# dbg-ram-4x8K.net
KiCad netlist of a schematic drawn in EAGLE
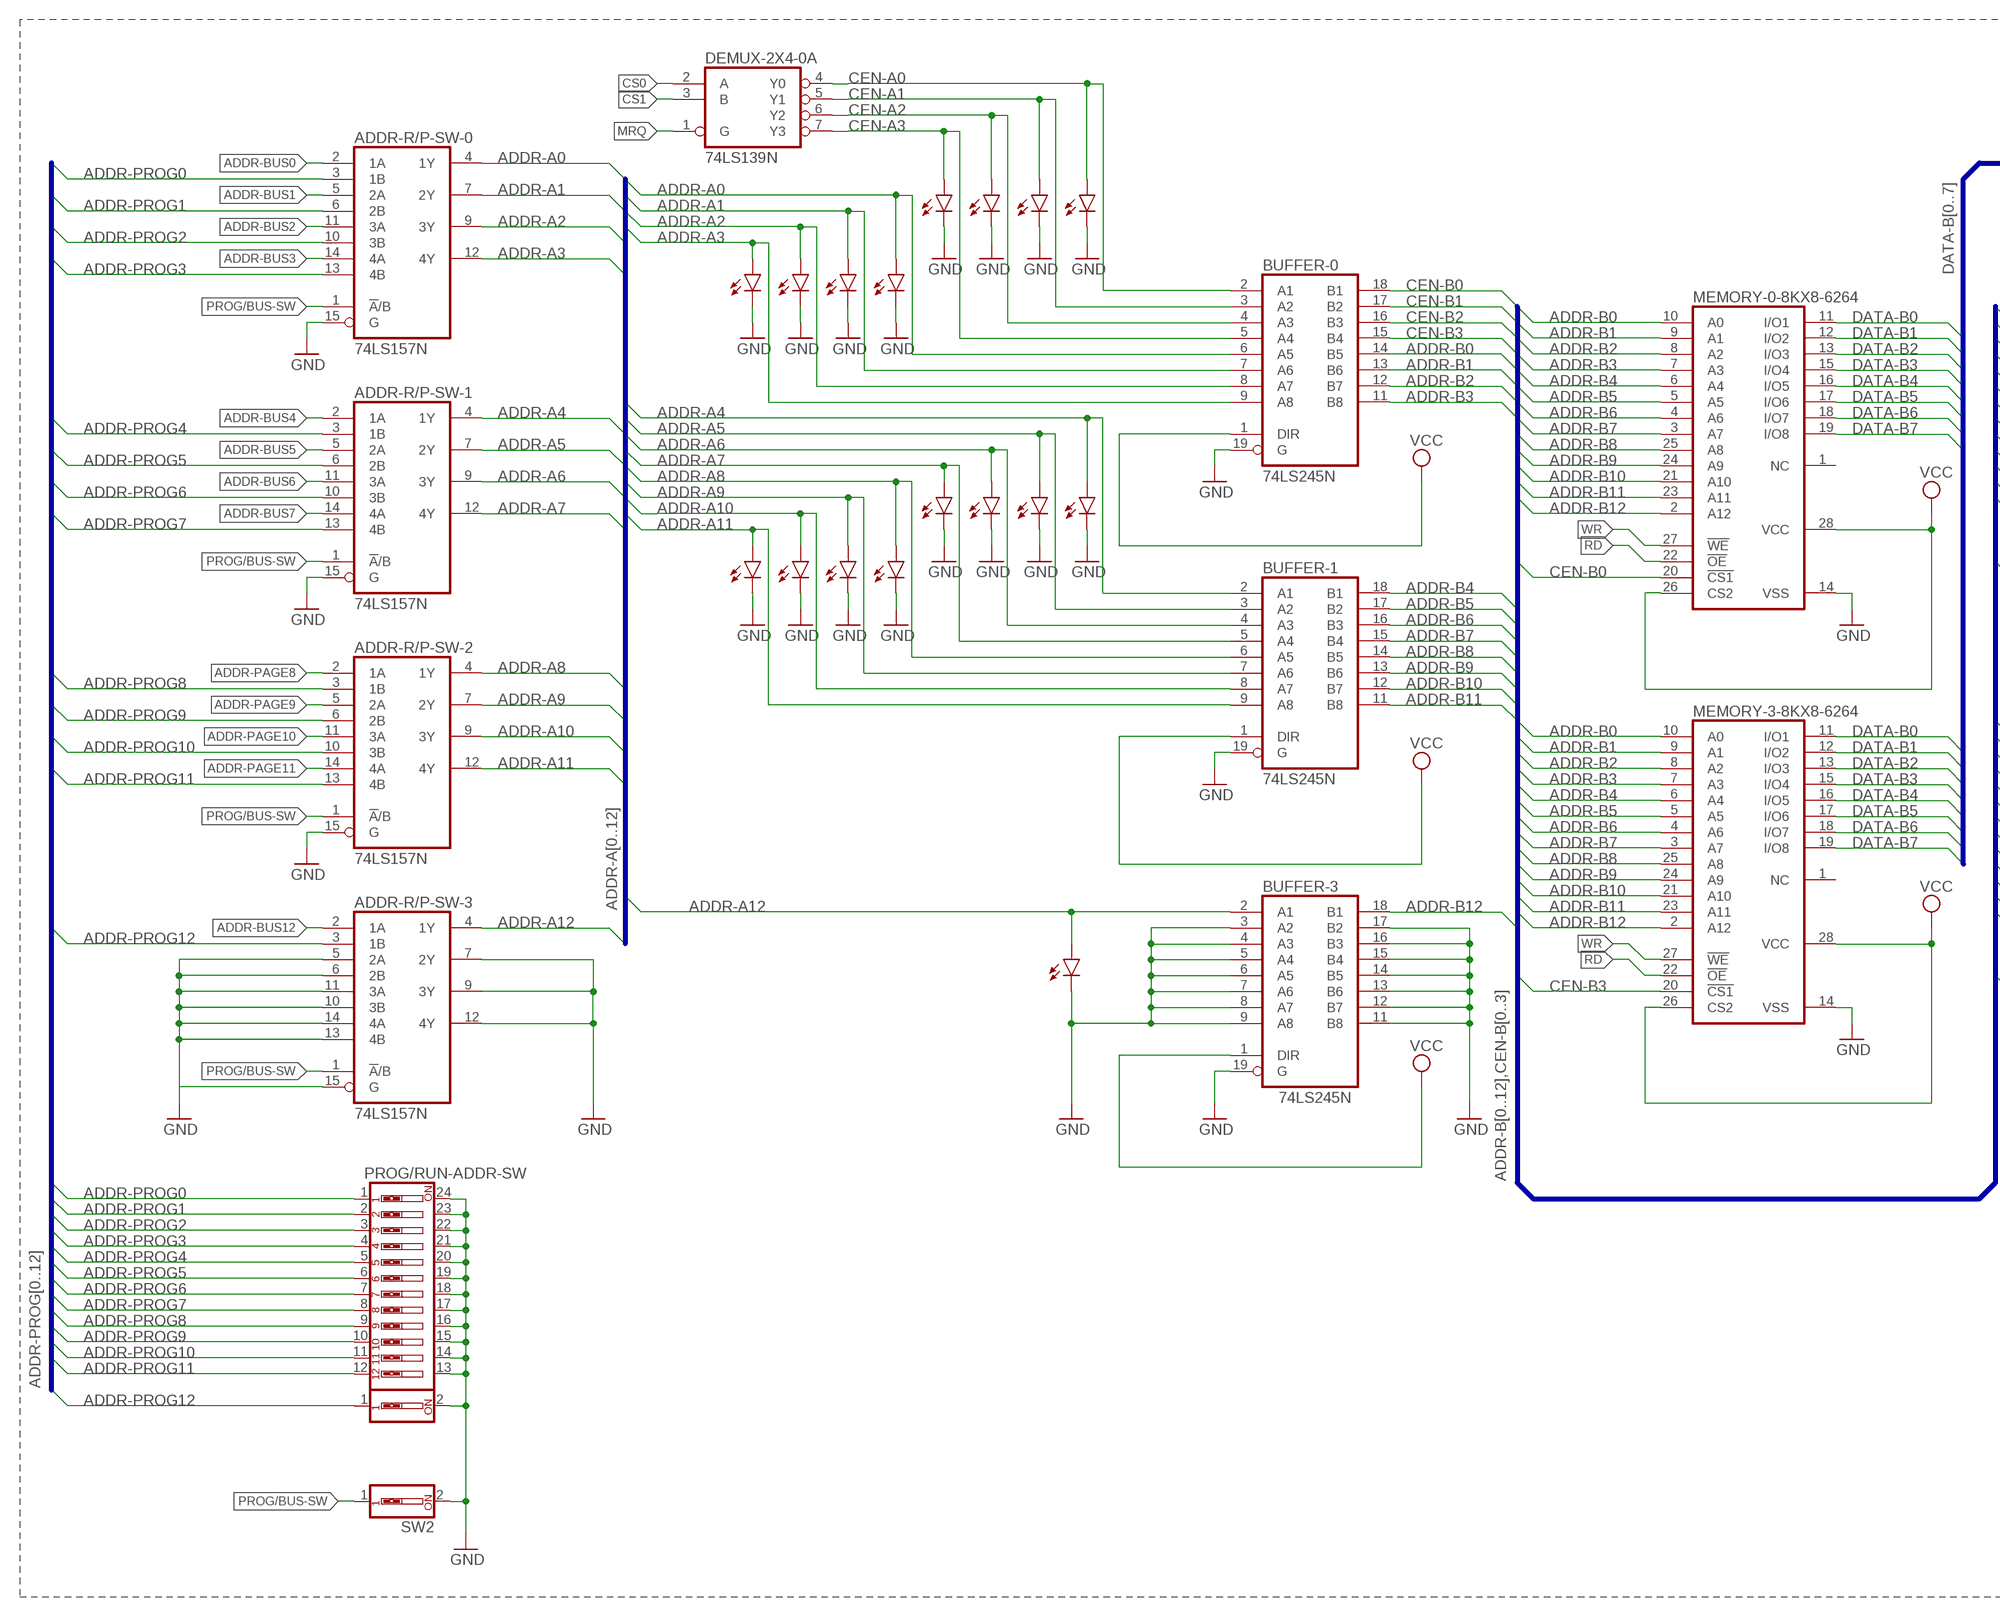
[diagram p0: schematic, sheet 1, part 1 of 2]
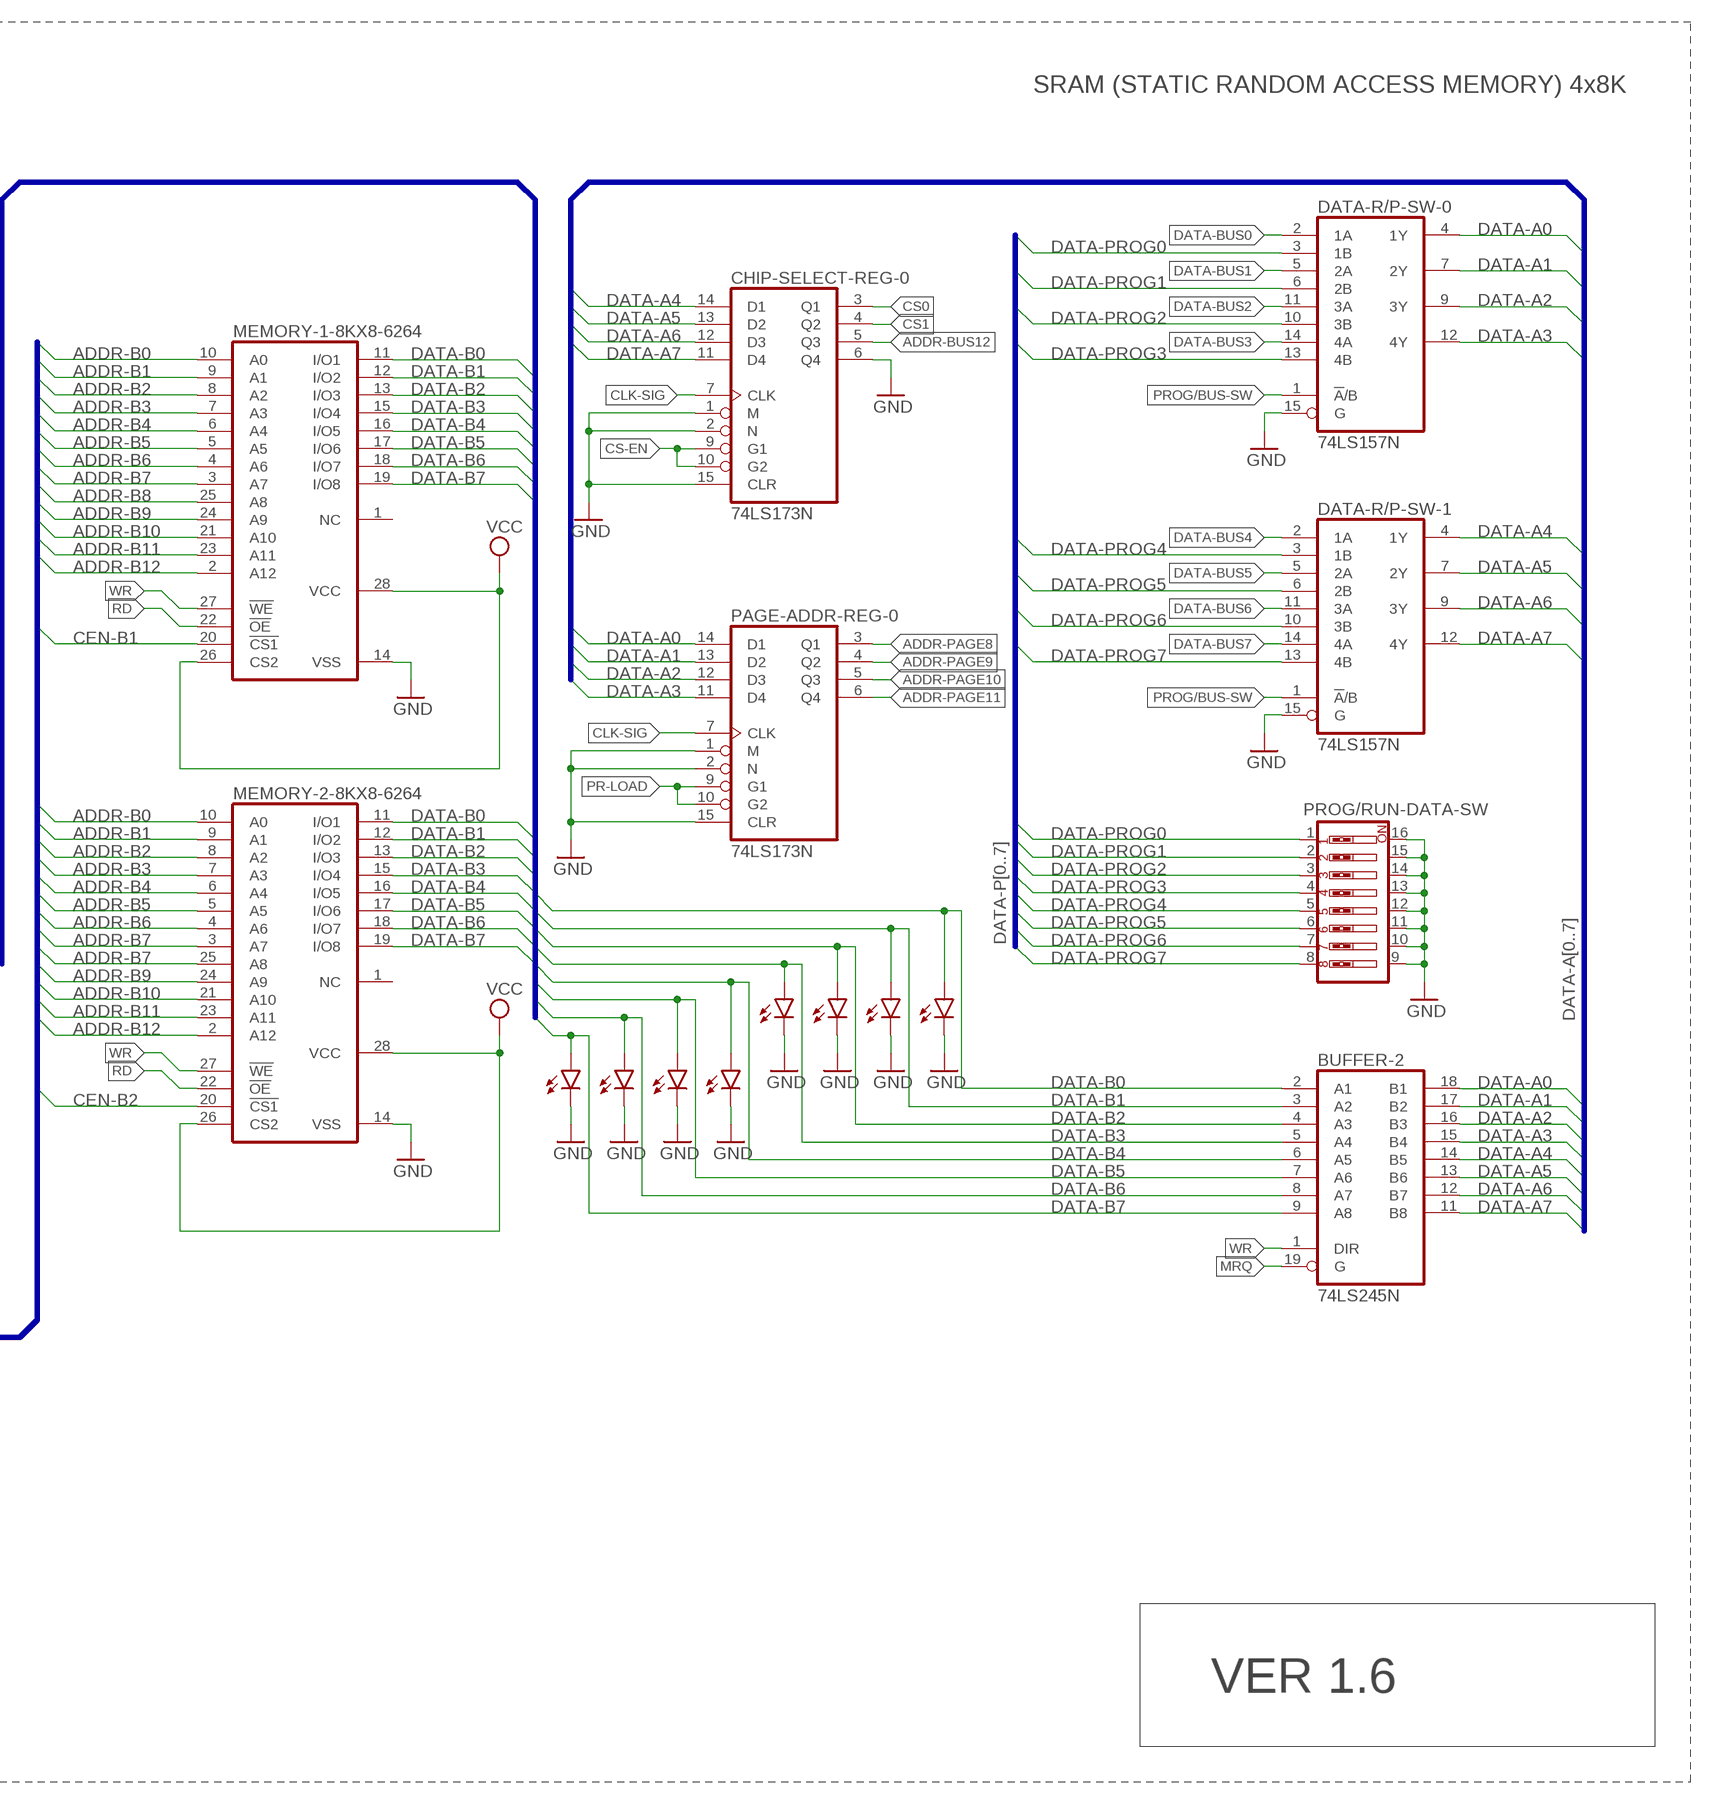
[diagram p1: schematic, sheet 1, part 2 of 2]

(export (version "E")
  (design (tool "Eeschema 10.0.6"))
  (components
    (comp (ref "ADDR-R/P-SW-0")
      (value "74LS157N")
      (footprint "eagle-import:DIL16")
      (libsource (lib "eagle-import") (part "74157NLS"))
    )
    (comp (ref "ADDR-R/P-SW-1")
      (value "74LS157N")
      (footprint "eagle-import:DIL16")
      (libsource (lib "eagle-import") (part "74157NLS"))
    )
    (comp (ref "ADDR-R/P-SW-2")
      (value "74LS157N")
      (footprint "eagle-import:DIL16")
      (libsource (lib "eagle-import") (part "74157NLS"))
    )
    (comp (ref "ADDR-R/P-SW-3")
      (value "74LS157N")
      (footprint "eagle-import:DIL16")
      (libsource (lib "eagle-import") (part "74157NLS"))
    )
    (comp (ref "BUFFER-0")
      (value "74LS245N")
      (footprint "eagle-import:DIL20")
      (libsource (lib "eagle-import") (part "74245NLS"))
    )
    (comp (ref "BUFFER-1")
      (value "74LS245N")
      (footprint "eagle-import:DIL20")
      (libsource (lib "eagle-import") (part "74245NLS"))
    )
    (comp (ref "BUFFER-2")
      (value "74LS245N")
      (footprint "eagle-import:DIL20")
      (libsource (lib "eagle-import") (part "74245NLS"))
    )
    (comp (ref "BUFFER-3")
      (value "74LS245N")
      (footprint "eagle-import:DIL20")
      (libsource (lib "eagle-import") (part "74245NLS"))
    )
    (comp (ref "CHIP-SELECT-REG-0")
      (value "74LS173N")
      (footprint "eagle-import:DIL16")
      (libsource (lib "eagle-import") (part "74173NLS"))
    )
    (comp (ref "DATA-R/P-SW-0")
      (value "74LS157N")
      (footprint "eagle-import:DIL16")
      (libsource (lib "eagle-import") (part "74157NLS"))
    )
    (comp (ref "DATA-R/P-SW-1")
      (value "74LS157N")
      (footprint "eagle-import:DIL16")
      (libsource (lib "eagle-import") (part "74157NLS"))
    )
    (comp (ref "DEMUX-2X4-0")
      (value "74LS139N")
      (footprint "eagle-import:DIL16")
      (libsource (lib "eagle-import") (part "74139NLS"))
    )
    (comp (ref "LED1")
      (value "LED5MM")
      (footprint "eagle-import:LED5MM")
      (libsource (lib "eagle-import") (part "LED5MM"))
    )
    (comp (ref "LED2")
      (value "LED5MM")
      (footprint "eagle-import:LED5MM")
      (libsource (lib "eagle-import") (part "LED5MM"))
    )
    (comp (ref "LED3")
      (value "LED5MM")
      (footprint "eagle-import:LED5MM")
      (libsource (lib "eagle-import") (part "LED5MM"))
    )
    (comp (ref "LED4")
      (value "LED5MM")
      (footprint "eagle-import:LED5MM")
      (libsource (lib "eagle-import") (part "LED5MM"))
    )
    (comp (ref "LED5")
      (value "LED5MM")
      (footprint "eagle-import:LED5MM")
      (libsource (lib "eagle-import") (part "LED5MM"))
    )
    (comp (ref "LED6")
      (value "LED5MM")
      (footprint "eagle-import:LED5MM")
      (libsource (lib "eagle-import") (part "LED5MM"))
    )
    (comp (ref "LED7")
      (value "LED5MM")
      (footprint "eagle-import:LED5MM")
      (libsource (lib "eagle-import") (part "LED5MM"))
    )
    (comp (ref "LED8")
      (value "LED5MM")
      (footprint "eagle-import:LED5MM")
      (libsource (lib "eagle-import") (part "LED5MM"))
    )
    (comp (ref "LED9")
      (value "LED5MM")
      (footprint "eagle-import:LED5MM")
      (libsource (lib "eagle-import") (part "LED5MM"))
    )
    (comp (ref "LED10")
      (value "LED5MM")
      (footprint "eagle-import:LED5MM")
      (libsource (lib "eagle-import") (part "LED5MM"))
    )
    (comp (ref "LED11")
      (value "LED5MM")
      (footprint "eagle-import:LED5MM")
      (libsource (lib "eagle-import") (part "LED5MM"))
    )
    (comp (ref "LED12")
      (value "LED5MM")
      (footprint "eagle-import:LED5MM")
      (libsource (lib "eagle-import") (part "LED5MM"))
    )
    (comp (ref "LED13")
      (value "LED5MM")
      (footprint "eagle-import:LED5MM")
      (libsource (lib "eagle-import") (part "LED5MM"))
    )
    (comp (ref "LED14")
      (value "LED5MM")
      (footprint "eagle-import:LED5MM")
      (libsource (lib "eagle-import") (part "LED5MM"))
    )
    (comp (ref "LED15")
      (value "LED5MM")
      (footprint "eagle-import:LED5MM")
      (libsource (lib "eagle-import") (part "LED5MM"))
    )
    (comp (ref "LED16")
      (value "LED5MM")
      (footprint "eagle-import:LED5MM")
      (libsource (lib "eagle-import") (part "LED5MM"))
    )
    (comp (ref "LED17")
      (value "LED5MM")
      (footprint "eagle-import:LED5MM")
      (libsource (lib "eagle-import") (part "LED5MM"))
    )
    (comp (ref "LED18")
      (value "LED5MM")
      (footprint "eagle-import:LED5MM")
      (libsource (lib "eagle-import") (part "LED5MM"))
    )
    (comp (ref "LED19")
      (value "LED5MM")
      (footprint "eagle-import:LED5MM")
      (libsource (lib "eagle-import") (part "LED5MM"))
    )
    (comp (ref "LED20")
      (value "LED5MM")
      (footprint "eagle-import:LED5MM")
      (libsource (lib "eagle-import") (part "LED5MM"))
    )
    (comp (ref "LED21")
      (value "LED5MM")
      (footprint "eagle-import:LED5MM")
      (libsource (lib "eagle-import") (part "LED5MM"))
    )
    (comp (ref "LED22")
      (value "LED5MM")
      (footprint "eagle-import:LED5MM")
      (libsource (lib "eagle-import") (part "LED5MM"))
    )
    (comp (ref "LED23")
      (value "LED5MM")
      (footprint "eagle-import:LED5MM")
      (libsource (lib "eagle-import") (part "LED5MM"))
    )
    (comp (ref "LED24")
      (value "LED5MM")
      (footprint "eagle-import:LED5MM")
      (libsource (lib "eagle-import") (part "LED5MM"))
    )
    (comp (ref "LED25")
      (value "LED5MM")
      (footprint "eagle-import:LED5MM")
      (libsource (lib "eagle-import") (part "LED5MM"))
    )
    (comp (ref "MEMORY-0-8KX8-6264")
      (value "6264A")
      (footprint "eagle-import:DIL28-6")
      (libsource (lib "eagle-import") (part "6264A"))
    )
    (comp (ref "MEMORY-1-8KX8-6264")
      (value "6264A")
      (footprint "eagle-import:DIL28-6")
      (libsource (lib "eagle-import") (part "6264A"))
    )
    (comp (ref "MEMORY-2-8KX8-6264")
      (value "6264A")
      (footprint "eagle-import:DIL28-6")
      (libsource (lib "eagle-import") (part "6264A"))
    )
    (comp (ref "MEMORY-3-8KX8-6264")
      (value "6264A")
      (footprint "eagle-import:DIL28-6")
      (libsource (lib "eagle-import") (part "6264A"))
    )
    (comp (ref "PAGE-ADDR-REG-0")
      (value "74LS173N")
      (footprint "eagle-import:DIL16")
      (libsource (lib "eagle-import") (part "74173NLS"))
    )
    (comp (ref "PROG/RUN-ADDR-SW")
      (value "SW_DIP-12")
      (footprint "eagle-import:EDG-12")
      (libsource (lib "eagle-import") (part "SW_DIP-12"))
    )
    (comp (ref "PROG/RUN-DATA-SW")
      (value "SW_DIP-8")
      (footprint "eagle-import:EDG-08")
      (libsource (lib "eagle-import") (part "SW_DIP-8"))
    )
    (comp (ref "SW2")
      (value "SW_DIP-1")
      (footprint "eagle-import:EDG-01")
      (libsource (lib "eagle-import") (part "SW_DIP-1"))
    )
    (comp (ref "SW3")
      (value "SW_DIP-1")
      (footprint "eagle-import:EDG-01")
      (libsource (lib "eagle-import") (part "SW_DIP-1"))
    )
  )
  (nets
    (net (code "9") (name "/ADDR-A0") (class "Default")
      (node (ref "ADDR-R/P-SW-0") (pin "4") (pinfunction "1Y_4") (pintype "output"))
      (node (ref "BUFFER-0") (pin "6") (pinfunction "A5_6") (pintype "bidirectional"))
      (node (ref "LED1") (pin "A") (pinfunction "A_A") (pintype "passive"))
    )
    (net (code "10") (name "/ADDR-A1") (class "Default")
      (node (ref "ADDR-R/P-SW-0") (pin "7") (pinfunction "2Y_7") (pintype "output"))
      (node (ref "BUFFER-0") (pin "7") (pinfunction "A6_7") (pintype "bidirectional"))
      (node (ref "LED2") (pin "A") (pinfunction "A_A") (pintype "passive"))
    )
    (net (code "11") (name "/ADDR-A2") (class "Default")
      (node (ref "ADDR-R/P-SW-0") (pin "9") (pinfunction "3Y_9") (pintype "output"))
      (node (ref "BUFFER-0") (pin "8") (pinfunction "A7_8") (pintype "bidirectional"))
      (node (ref "LED3") (pin "A") (pinfunction "A_A") (pintype "passive"))
    )
    (net (code "12") (name "/ADDR-A3") (class "Default")
      (node (ref "ADDR-R/P-SW-0") (pin "12") (pinfunction "4Y_12") (pintype "output"))
      (node (ref "BUFFER-0") (pin "9") (pinfunction "A8_9") (pintype "bidirectional"))
      (node (ref "LED4") (pin "A") (pinfunction "A_A") (pintype "passive"))
    )
    (net (code "13") (name "/ADDR-A4") (class "Default")
      (node (ref "ADDR-R/P-SW-1") (pin "4") (pinfunction "1Y_4") (pintype "output"))
      (node (ref "BUFFER-1") (pin "2") (pinfunction "A1_2") (pintype "bidirectional"))
      (node (ref "LED5") (pin "A") (pinfunction "A_A") (pintype "passive"))
    )
    (net (code "14") (name "/ADDR-A5") (class "Default")
      (node (ref "ADDR-R/P-SW-1") (pin "7") (pinfunction "2Y_7") (pintype "output"))
      (node (ref "BUFFER-1") (pin "3") (pinfunction "A2_3") (pintype "bidirectional"))
      (node (ref "LED6") (pin "A") (pinfunction "A_A") (pintype "passive"))
    )
    (net (code "15") (name "/ADDR-A6") (class "Default")
      (node (ref "ADDR-R/P-SW-1") (pin "9") (pinfunction "3Y_9") (pintype "output"))
      (node (ref "BUFFER-1") (pin "4") (pinfunction "A3_4") (pintype "bidirectional"))
      (node (ref "LED10") (pin "A") (pinfunction "A_A") (pintype "passive"))
    )
    (net (code "16") (name "/ADDR-A7") (class "Default")
      (node (ref "ADDR-R/P-SW-1") (pin "12") (pinfunction "4Y_12") (pintype "output"))
      (node (ref "BUFFER-1") (pin "5") (pinfunction "A4_5") (pintype "bidirectional"))
      (node (ref "LED7") (pin "A") (pinfunction "A_A") (pintype "passive"))
    )
    (net (code "17") (name "/ADDR-A8") (class "Default")
      (node (ref "ADDR-R/P-SW-2") (pin "4") (pinfunction "1Y_4") (pintype "output"))
      (node (ref "BUFFER-1") (pin "6") (pinfunction "A5_6") (pintype "bidirectional"))
      (node (ref "LED8") (pin "A") (pinfunction "A_A") (pintype "passive"))
    )
    (net (code "18") (name "/ADDR-A9") (class "Default")
      (node (ref "ADDR-R/P-SW-2") (pin "7") (pinfunction "2Y_7") (pintype "output"))
      (node (ref "BUFFER-1") (pin "7") (pinfunction "A6_7") (pintype "bidirectional"))
      (node (ref "LED9") (pin "A") (pinfunction "A_A") (pintype "passive"))
    )
    (net (code "19") (name "/ADDR-A10") (class "Default")
      (node (ref "ADDR-R/P-SW-2") (pin "9") (pinfunction "3Y_9") (pintype "output"))
      (node (ref "BUFFER-1") (pin "8") (pinfunction "A7_8") (pintype "bidirectional"))
      (node (ref "LED15") (pin "A") (pinfunction "A_A") (pintype "passive"))
    )
    (net (code "20") (name "/ADDR-A11") (class "Default")
      (node (ref "ADDR-R/P-SW-2") (pin "12") (pinfunction "4Y_12") (pintype "output"))
      (node (ref "BUFFER-1") (pin "9") (pinfunction "A8_9") (pintype "bidirectional"))
      (node (ref "LED17") (pin "A") (pinfunction "A_A") (pintype "passive"))
    )
    (net (code "21") (name "/ADDR-A12") (class "Default")
      (node (ref "ADDR-R/P-SW-3") (pin "4") (pinfunction "1Y_4") (pintype "output"))
      (node (ref "BUFFER-3") (pin "2") (pinfunction "A1_2") (pintype "bidirectional"))
      (node (ref "LED16") (pin "A") (pinfunction "A_A") (pintype "passive"))
    )
    (net (code "23") (name "/ADDR-B0") (class "Default")
      (node (ref "BUFFER-0") (pin "14") (pinfunction "B5_14") (pintype "bidirectional"))
      (node (ref "MEMORY-0-8KX8-6264") (pin "10") (pinfunction "A0_10") (pintype "input"))
      (node (ref "MEMORY-1-8KX8-6264") (pin "10") (pinfunction "A0_10") (pintype "input"))
      (node (ref "MEMORY-2-8KX8-6264") (pin "10") (pinfunction "A0_10") (pintype "input"))
      (node (ref "MEMORY-3-8KX8-6264") (pin "10") (pinfunction "A0_10") (pintype "input"))
    )
    (net (code "24") (name "/ADDR-B1") (class "Default")
      (node (ref "BUFFER-0") (pin "13") (pinfunction "B6_13") (pintype "bidirectional"))
      (node (ref "MEMORY-0-8KX8-6264") (pin "9") (pinfunction "A1_9") (pintype "input"))
      (node (ref "MEMORY-1-8KX8-6264") (pin "9") (pinfunction "A1_9") (pintype "input"))
      (node (ref "MEMORY-2-8KX8-6264") (pin "9") (pinfunction "A1_9") (pintype "input"))
      (node (ref "MEMORY-3-8KX8-6264") (pin "9") (pinfunction "A1_9") (pintype "input"))
    )
    (net (code "25") (name "/ADDR-B2") (class "Default")
      (node (ref "BUFFER-0") (pin "12") (pinfunction "B7_12") (pintype "bidirectional"))
      (node (ref "MEMORY-0-8KX8-6264") (pin "8") (pinfunction "A2_8") (pintype "input"))
      (node (ref "MEMORY-1-8KX8-6264") (pin "8") (pinfunction "A2_8") (pintype "input"))
      (node (ref "MEMORY-2-8KX8-6264") (pin "8") (pinfunction "A2_8") (pintype "input"))
      (node (ref "MEMORY-3-8KX8-6264") (pin "8") (pinfunction "A2_8") (pintype "input"))
    )
    (net (code "26") (name "/ADDR-B3") (class "Default")
      (node (ref "BUFFER-0") (pin "11") (pinfunction "B8_11") (pintype "bidirectional"))
      (node (ref "MEMORY-0-8KX8-6264") (pin "7") (pinfunction "A3_7") (pintype "input"))
      (node (ref "MEMORY-1-8KX8-6264") (pin "7") (pinfunction "A3_7") (pintype "input"))
      (node (ref "MEMORY-2-8KX8-6264") (pin "7") (pinfunction "A3_7") (pintype "input"))
      (node (ref "MEMORY-3-8KX8-6264") (pin "7") (pinfunction "A3_7") (pintype "input"))
    )
    (net (code "27") (name "/ADDR-B4") (class "Default")
      (node (ref "BUFFER-1") (pin "18") (pinfunction "B1_18") (pintype "bidirectional"))
      (node (ref "MEMORY-0-8KX8-6264") (pin "6") (pinfunction "A4_6") (pintype "input"))
      (node (ref "MEMORY-1-8KX8-6264") (pin "6") (pinfunction "A4_6") (pintype "input"))
      (node (ref "MEMORY-2-8KX8-6264") (pin "6") (pinfunction "A4_6") (pintype "input"))
      (node (ref "MEMORY-3-8KX8-6264") (pin "6") (pinfunction "A4_6") (pintype "input"))
    )
    (net (code "28") (name "/ADDR-B5") (class "Default")
      (node (ref "BUFFER-1") (pin "17") (pinfunction "B2_17") (pintype "bidirectional"))
      (node (ref "MEMORY-0-8KX8-6264") (pin "5") (pinfunction "A5_5") (pintype "input"))
      (node (ref "MEMORY-1-8KX8-6264") (pin "5") (pinfunction "A5_5") (pintype "input"))
      (node (ref "MEMORY-2-8KX8-6264") (pin "5") (pinfunction "A5_5") (pintype "input"))
      (node (ref "MEMORY-3-8KX8-6264") (pin "5") (pinfunction "A5_5") (pintype "input"))
    )
    (net (code "29") (name "/ADDR-B6") (class "Default")
      (node (ref "BUFFER-1") (pin "16") (pinfunction "B3_16") (pintype "bidirectional"))
      (node (ref "MEMORY-0-8KX8-6264") (pin "4") (pinfunction "A6_4") (pintype "input"))
      (node (ref "MEMORY-1-8KX8-6264") (pin "4") (pinfunction "A6_4") (pintype "input"))
      (node (ref "MEMORY-2-8KX8-6264") (pin "4") (pinfunction "A6_4") (pintype "input"))
      (node (ref "MEMORY-3-8KX8-6264") (pin "4") (pinfunction "A6_4") (pintype "input"))
    )
    (net (code "30") (name "/ADDR-B7") (class "Default")
      (node (ref "BUFFER-1") (pin "15") (pinfunction "B4_15") (pintype "bidirectional"))
      (node (ref "MEMORY-0-8KX8-6264") (pin "3") (pinfunction "A7_3") (pintype "input"))
      (node (ref "MEMORY-1-8KX8-6264") (pin "3") (pinfunction "A7_3") (pintype "input"))
      (node (ref "MEMORY-2-8KX8-6264") (pin "25") (pinfunction "A8_25") (pintype "input"))
      (node (ref "MEMORY-2-8KX8-6264") (pin "3") (pinfunction "A7_3") (pintype "input"))
      (node (ref "MEMORY-3-8KX8-6264") (pin "3") (pinfunction "A7_3") (pintype "input"))
    )
    (net (code "31") (name "/ADDR-B8") (class "Default")
      (node (ref "BUFFER-1") (pin "14") (pinfunction "B5_14") (pintype "bidirectional"))
      (node (ref "MEMORY-0-8KX8-6264") (pin "25") (pinfunction "A8_25") (pintype "input"))
      (node (ref "MEMORY-1-8KX8-6264") (pin "25") (pinfunction "A8_25") (pintype "input"))
      (node (ref "MEMORY-3-8KX8-6264") (pin "25") (pinfunction "A8_25") (pintype "input"))
    )
    (net (code "32") (name "/ADDR-B9") (class "Default")
      (node (ref "BUFFER-1") (pin "13") (pinfunction "B6_13") (pintype "bidirectional"))
      (node (ref "MEMORY-0-8KX8-6264") (pin "24") (pinfunction "A9_24") (pintype "input"))
      (node (ref "MEMORY-1-8KX8-6264") (pin "24") (pinfunction "A9_24") (pintype "input"))
      (node (ref "MEMORY-2-8KX8-6264") (pin "24") (pinfunction "A9_24") (pintype "input"))
      (node (ref "MEMORY-3-8KX8-6264") (pin "24") (pinfunction "A9_24") (pintype "input"))
    )
    (net (code "33") (name "/ADDR-B10") (class "Default")
      (node (ref "BUFFER-1") (pin "12") (pinfunction "B7_12") (pintype "bidirectional"))
      (node (ref "MEMORY-0-8KX8-6264") (pin "21") (pinfunction "A10_21") (pintype "input"))
      (node (ref "MEMORY-1-8KX8-6264") (pin "21") (pinfunction "A10_21") (pintype "input"))
      (node (ref "MEMORY-2-8KX8-6264") (pin "21") (pinfunction "A10_21") (pintype "input"))
      (node (ref "MEMORY-3-8KX8-6264") (pin "21") (pinfunction "A10_21") (pintype "input"))
    )
    (net (code "34") (name "/ADDR-B11") (class "Default")
      (node (ref "BUFFER-1") (pin "11") (pinfunction "B8_11") (pintype "bidirectional"))
      (node (ref "MEMORY-0-8KX8-6264") (pin "23") (pinfunction "A11_23") (pintype "input"))
      (node (ref "MEMORY-1-8KX8-6264") (pin "23") (pinfunction "A11_23") (pintype "input"))
      (node (ref "MEMORY-2-8KX8-6264") (pin "23") (pinfunction "A11_23") (pintype "input"))
      (node (ref "MEMORY-3-8KX8-6264") (pin "23") (pinfunction "A11_23") (pintype "input"))
    )
    (net (code "35") (name "/ADDR-B12") (class "Default")
      (node (ref "BUFFER-3") (pin "18") (pinfunction "B1_18") (pintype "bidirectional"))
      (node (ref "MEMORY-0-8KX8-6264") (pin "2") (pinfunction "A12_2") (pintype "input"))
      (node (ref "MEMORY-1-8KX8-6264") (pin "2") (pinfunction "A12_2") (pintype "input"))
      (node (ref "MEMORY-2-8KX8-6264") (pin "2") (pinfunction "A12_2") (pintype "input"))
      (node (ref "MEMORY-3-8KX8-6264") (pin "2") (pinfunction "A12_2") (pintype "input"))
    )
    (net (code "36") (name "/ADDR-PROG0") (class "Default")
      (node (ref "ADDR-R/P-SW-0") (pin "3") (pinfunction "1B_3") (pintype "input"))
      (node (ref "PROG/RUN-ADDR-SW") (pin "1") (pinfunction "1_1") (pintype "passive"))
    )
    (net (code "37") (name "/ADDR-PROG1") (class "Default")
      (node (ref "ADDR-R/P-SW-0") (pin "6") (pinfunction "2B_6") (pintype "input"))
      (node (ref "PROG/RUN-ADDR-SW") (pin "2") (pinfunction "2_2") (pintype "passive"))
    )
    (net (code "38") (name "/ADDR-PROG2") (class "Default")
      (node (ref "ADDR-R/P-SW-0") (pin "10") (pinfunction "3B_10") (pintype "input"))
      (node (ref "PROG/RUN-ADDR-SW") (pin "3") (pinfunction "3_3") (pintype "passive"))
    )
    (net (code "39") (name "/ADDR-PROG3") (class "Default")
      (node (ref "ADDR-R/P-SW-0") (pin "13") (pinfunction "4B_13") (pintype "input"))
      (node (ref "PROG/RUN-ADDR-SW") (pin "4") (pinfunction "4_4") (pintype "passive"))
    )
    (net (code "40") (name "/ADDR-PROG4") (class "Default")
      (node (ref "ADDR-R/P-SW-1") (pin "3") (pinfunction "1B_3") (pintype "input"))
      (node (ref "PROG/RUN-ADDR-SW") (pin "5") (pinfunction "5_5") (pintype "passive"))
    )
    (net (code "41") (name "/ADDR-PROG5") (class "Default")
      (node (ref "ADDR-R/P-SW-1") (pin "6") (pinfunction "2B_6") (pintype "input"))
      (node (ref "PROG/RUN-ADDR-SW") (pin "6") (pinfunction "6_6") (pintype "passive"))
    )
    (net (code "42") (name "/ADDR-PROG6") (class "Default")
      (node (ref "ADDR-R/P-SW-1") (pin "10") (pinfunction "3B_10") (pintype "input"))
      (node (ref "PROG/RUN-ADDR-SW") (pin "7") (pinfunction "7_7") (pintype "passive"))
    )
    (net (code "43") (name "/ADDR-PROG7") (class "Default")
      (node (ref "ADDR-R/P-SW-1") (pin "13") (pinfunction "4B_13") (pintype "input"))
      (node (ref "PROG/RUN-ADDR-SW") (pin "8") (pinfunction "8_8") (pintype "passive"))
    )
    (net (code "44") (name "/ADDR-PROG8") (class "Default")
      (node (ref "ADDR-R/P-SW-2") (pin "3") (pinfunction "1B_3") (pintype "input"))
      (node (ref "PROG/RUN-ADDR-SW") (pin "9") (pinfunction "9_9") (pintype "passive"))
    )
    (net (code "45") (name "/ADDR-PROG9") (class "Default")
      (node (ref "ADDR-R/P-SW-2") (pin "6") (pinfunction "2B_6") (pintype "input"))
      (node (ref "PROG/RUN-ADDR-SW") (pin "10") (pinfunction "10_10") (pintype "passive"))
    )
    (net (code "46") (name "/ADDR-PROG10") (class "Default")
      (node (ref "ADDR-R/P-SW-2") (pin "10") (pinfunction "3B_10") (pintype "input"))
      (node (ref "PROG/RUN-ADDR-SW") (pin "11") (pinfunction "11_11") (pintype "passive"))
    )
    (net (code "47") (name "/ADDR-PROG11") (class "Default")
      (node (ref "ADDR-R/P-SW-2") (pin "13") (pinfunction "4B_13") (pintype "input"))
      (node (ref "PROG/RUN-ADDR-SW") (pin "12") (pinfunction "12_12") (pintype "passive"))
    )
    (net (code "48") (name "/ADDR-PROG12") (class "Default")
      (node (ref "ADDR-R/P-SW-3") (pin "3") (pinfunction "1B_3") (pintype "input"))
      (node (ref "SW3") (pin "1") (pinfunction "1_1") (pintype "passive"))
    )
    (net (code "50") (name "/CEN-A0") (class "Default")
      (node (ref "BUFFER-0") (pin "2") (pinfunction "A1_2") (pintype "bidirectional"))
      (node (ref "DEMUX-2X4-0") (pin "4") (pinfunction "Y0_4") (pintype "output"))
      (node (ref "LED11") (pin "A") (pinfunction "A_A") (pintype "passive"))
    )
    (net (code "51") (name "/CEN-A1") (class "Default")
      (node (ref "BUFFER-0") (pin "3") (pinfunction "A2_3") (pintype "bidirectional"))
      (node (ref "DEMUX-2X4-0") (pin "5") (pinfunction "Y1_5") (pintype "output"))
      (node (ref "LED12") (pin "A") (pinfunction "A_A") (pintype "passive"))
    )
    (net (code "52") (name "/CEN-A2") (class "Default")
      (node (ref "BUFFER-0") (pin "4") (pinfunction "A3_4") (pintype "bidirectional"))
      (node (ref "DEMUX-2X4-0") (pin "6") (pinfunction "Y2_6") (pintype "output"))
      (node (ref "LED13") (pin "A") (pinfunction "A_A") (pintype "passive"))
    )
    (net (code "53") (name "/CEN-A3") (class "Default")
      (node (ref "BUFFER-0") (pin "5") (pinfunction "A4_5") (pintype "bidirectional"))
      (node (ref "DEMUX-2X4-0") (pin "7") (pinfunction "Y3_7") (pintype "output"))
      (node (ref "LED14") (pin "A") (pinfunction "A_A") (pintype "passive"))
    )
    (net (code "54") (name "/CEN-B0") (class "Default")
      (node (ref "BUFFER-0") (pin "18") (pinfunction "B1_18") (pintype "bidirectional"))
      (node (ref "MEMORY-0-8KX8-6264") (pin "20") (pinfunction "~{CS1}_20") (pintype "input"))
    )
    (net (code "55") (name "/CEN-B1") (class "Default")
      (node (ref "BUFFER-0") (pin "17") (pinfunction "B2_17") (pintype "bidirectional"))
      (node (ref "MEMORY-1-8KX8-6264") (pin "20") (pinfunction "~{CS1}_20") (pintype "input"))
    )
    (net (code "56") (name "/CEN-B2") (class "Default")
      (node (ref "BUFFER-0") (pin "16") (pinfunction "B3_16") (pintype "bidirectional"))
      (node (ref "MEMORY-2-8KX8-6264") (pin "20") (pinfunction "~{CS1}_20") (pintype "input"))
    )
    (net (code "57") (name "/CEN-B3") (class "Default")
      (node (ref "BUFFER-0") (pin "15") (pinfunction "B4_15") (pintype "bidirectional"))
      (node (ref "MEMORY-3-8KX8-6264") (pin "20") (pinfunction "~{CS1}_20") (pintype "input"))
    )
    (net (code "58") (name "/DATA-A0") (class "Default")
      (node (ref "BUFFER-2") (pin "18") (pinfunction "B1_18") (pintype "bidirectional"))
      (node (ref "DATA-R/P-SW-0") (pin "4") (pinfunction "1Y_4") (pintype "output"))
      (node (ref "PAGE-ADDR-REG-0") (pin "14") (pinfunction "D1_14") (pintype "input"))
    )
    (net (code "59") (name "/DATA-A1") (class "Default")
      (node (ref "BUFFER-2") (pin "17") (pinfunction "B2_17") (pintype "bidirectional"))
      (node (ref "DATA-R/P-SW-0") (pin "7") (pinfunction "2Y_7") (pintype "output"))
      (node (ref "PAGE-ADDR-REG-0") (pin "13") (pinfunction "D2_13") (pintype "input"))
    )
    (net (code "60") (name "/DATA-A2") (class "Default")
      (node (ref "BUFFER-2") (pin "16") (pinfunction "B3_16") (pintype "bidirectional"))
      (node (ref "DATA-R/P-SW-0") (pin "9") (pinfunction "3Y_9") (pintype "output"))
      (node (ref "PAGE-ADDR-REG-0") (pin "12") (pinfunction "D3_12") (pintype "input"))
    )
    (net (code "61") (name "/DATA-A3") (class "Default")
      (node (ref "BUFFER-2") (pin "15") (pinfunction "B4_15") (pintype "bidirectional"))
      (node (ref "DATA-R/P-SW-0") (pin "12") (pinfunction "4Y_12") (pintype "output"))
      (node (ref "PAGE-ADDR-REG-0") (pin "11") (pinfunction "D4_11") (pintype "input"))
    )
    (net (code "62") (name "/DATA-A4") (class "Default")
      (node (ref "BUFFER-2") (pin "14") (pinfunction "B5_14") (pintype "bidirectional"))
      (node (ref "CHIP-SELECT-REG-0") (pin "14") (pinfunction "D1_14") (pintype "input"))
      (node (ref "DATA-R/P-SW-1") (pin "4") (pinfunction "1Y_4") (pintype "output"))
    )
    (net (code "63") (name "/DATA-A5") (class "Default")
      (node (ref "BUFFER-2") (pin "13") (pinfunction "B6_13") (pintype "bidirectional"))
      (node (ref "CHIP-SELECT-REG-0") (pin "13") (pinfunction "D2_13") (pintype "input"))
      (node (ref "DATA-R/P-SW-1") (pin "7") (pinfunction "2Y_7") (pintype "output"))
    )
    (net (code "64") (name "/DATA-A6") (class "Default")
      (node (ref "BUFFER-2") (pin "12") (pinfunction "B7_12") (pintype "bidirectional"))
      (node (ref "CHIP-SELECT-REG-0") (pin "12") (pinfunction "D3_12") (pintype "input"))
      (node (ref "DATA-R/P-SW-1") (pin "9") (pinfunction "3Y_9") (pintype "output"))
    )
    (net (code "65") (name "/DATA-A7") (class "Default")
      (node (ref "BUFFER-2") (pin "11") (pinfunction "B8_11") (pintype "bidirectional"))
      (node (ref "CHIP-SELECT-REG-0") (pin "11") (pinfunction "D4_11") (pintype "input"))
      (node (ref "DATA-R/P-SW-1") (pin "12") (pinfunction "4Y_12") (pintype "output"))
    )
    (net (code "67") (name "/DATA-B0") (class "Default")
      (node (ref "BUFFER-2") (pin "2") (pinfunction "A1_2") (pintype "bidirectional"))
      (node (ref "LED25") (pin "A") (pinfunction "A_A") (pintype "passive"))
      (node (ref "MEMORY-0-8KX8-6264") (pin "11") (pinfunction "I/O1_11") (pintype "bidirectional"))
      (node (ref "MEMORY-1-8KX8-6264") (pin "11") (pinfunction "I/O1_11") (pintype "bidirectional"))
      (node (ref "MEMORY-2-8KX8-6264") (pin "11") (pinfunction "I/O1_11") (pintype "bidirectional"))
      (node (ref "MEMORY-3-8KX8-6264") (pin "11") (pinfunction "I/O1_11") (pintype "bidirectional"))
    )
    (net (code "68") (name "/DATA-B1") (class "Default")
      (node (ref "BUFFER-2") (pin "3") (pinfunction "A2_3") (pintype "bidirectional"))
      (node (ref "LED24") (pin "A") (pinfunction "A_A") (pintype "passive"))
      (node (ref "MEMORY-0-8KX8-6264") (pin "12") (pinfunction "I/O2_12") (pintype "bidirectional"))
      (node (ref "MEMORY-1-8KX8-6264") (pin "12") (pinfunction "I/O2_12") (pintype "bidirectional"))
      (node (ref "MEMORY-2-8KX8-6264") (pin "12") (pinfunction "I/O2_12") (pintype "bidirectional"))
      (node (ref "MEMORY-3-8KX8-6264") (pin "12") (pinfunction "I/O2_12") (pintype "bidirectional"))
    )
    (net (code "69") (name "/DATA-B2") (class "Default")
      (node (ref "BUFFER-2") (pin "4") (pinfunction "A3_4") (pintype "bidirectional"))
      (node (ref "LED23") (pin "A") (pinfunction "A_A") (pintype "passive"))
      (node (ref "MEMORY-0-8KX8-6264") (pin "13") (pinfunction "I/O3_13") (pintype "bidirectional"))
      (node (ref "MEMORY-1-8KX8-6264") (pin "13") (pinfunction "I/O3_13") (pintype "bidirectional"))
      (node (ref "MEMORY-2-8KX8-6264") (pin "13") (pinfunction "I/O3_13") (pintype "bidirectional"))
      (node (ref "MEMORY-3-8KX8-6264") (pin "13") (pinfunction "I/O3_13") (pintype "bidirectional"))
    )
    (net (code "70") (name "/DATA-B3") (class "Default")
      (node (ref "BUFFER-2") (pin "5") (pinfunction "A4_5") (pintype "bidirectional"))
      (node (ref "LED22") (pin "A") (pinfunction "A_A") (pintype "passive"))
      (node (ref "MEMORY-0-8KX8-6264") (pin "15") (pinfunction "I/O4_15") (pintype "bidirectional"))
      (node (ref "MEMORY-1-8KX8-6264") (pin "15") (pinfunction "I/O4_15") (pintype "bidirectional"))
      (node (ref "MEMORY-2-8KX8-6264") (pin "15") (pinfunction "I/O4_15") (pintype "bidirectional"))
      (node (ref "MEMORY-3-8KX8-6264") (pin "15") (pinfunction "I/O4_15") (pintype "bidirectional"))
    )
    (net (code "71") (name "/DATA-B4") (class "Default")
      (node (ref "BUFFER-2") (pin "6") (pinfunction "A5_6") (pintype "bidirectional"))
      (node (ref "LED21") (pin "A") (pinfunction "A_A") (pintype "passive"))
      (node (ref "MEMORY-0-8KX8-6264") (pin "16") (pinfunction "I/O5_16") (pintype "bidirectional"))
      (node (ref "MEMORY-1-8KX8-6264") (pin "16") (pinfunction "I/O5_16") (pintype "bidirectional"))
      (node (ref "MEMORY-2-8KX8-6264") (pin "16") (pinfunction "I/O5_16") (pintype "bidirectional"))
      (node (ref "MEMORY-3-8KX8-6264") (pin "16") (pinfunction "I/O5_16") (pintype "bidirectional"))
    )
    (net (code "72") (name "/DATA-B5") (class "Default")
      (node (ref "BUFFER-2") (pin "7") (pinfunction "A6_7") (pintype "bidirectional"))
      (node (ref "LED20") (pin "A") (pinfunction "A_A") (pintype "passive"))
      (node (ref "MEMORY-0-8KX8-6264") (pin "17") (pinfunction "I/O6_17") (pintype "bidirectional"))
      (node (ref "MEMORY-1-8KX8-6264") (pin "17") (pinfunction "I/O6_17") (pintype "bidirectional"))
      (node (ref "MEMORY-2-8KX8-6264") (pin "17") (pinfunction "I/O6_17") (pintype "bidirectional"))
      (node (ref "MEMORY-3-8KX8-6264") (pin "17") (pinfunction "I/O6_17") (pintype "bidirectional"))
    )
    (net (code "73") (name "/DATA-B6") (class "Default")
      (node (ref "BUFFER-2") (pin "8") (pinfunction "A7_8") (pintype "bidirectional"))
      (node (ref "LED19") (pin "A") (pinfunction "A_A") (pintype "passive"))
      (node (ref "MEMORY-0-8KX8-6264") (pin "18") (pinfunction "I/O7_18") (pintype "bidirectional"))
      (node (ref "MEMORY-1-8KX8-6264") (pin "18") (pinfunction "I/O7_18") (pintype "bidirectional"))
      (node (ref "MEMORY-2-8KX8-6264") (pin "18") (pinfunction "I/O7_18") (pintype "bidirectional"))
      (node (ref "MEMORY-3-8KX8-6264") (pin "18") (pinfunction "I/O7_18") (pintype "bidirectional"))
    )
    (net (code "74") (name "/DATA-B7") (class "Default")
      (node (ref "BUFFER-2") (pin "9") (pinfunction "A8_9") (pintype "bidirectional"))
      (node (ref "LED18") (pin "A") (pinfunction "A_A") (pintype "passive"))
      (node (ref "MEMORY-0-8KX8-6264") (pin "19") (pinfunction "I/O8_19") (pintype "bidirectional"))
      (node (ref "MEMORY-1-8KX8-6264") (pin "19") (pinfunction "I/O8_19") (pintype "bidirectional"))
      (node (ref "MEMORY-2-8KX8-6264") (pin "19") (pinfunction "I/O8_19") (pintype "bidirectional"))
      (node (ref "MEMORY-3-8KX8-6264") (pin "19") (pinfunction "I/O8_19") (pintype "bidirectional"))
    )
    (net (code "76") (name "/DATA-PROG0") (class "Default")
      (node (ref "DATA-R/P-SW-0") (pin "3") (pinfunction "1B_3") (pintype "input"))
      (node (ref "PROG/RUN-DATA-SW") (pin "1") (pinfunction "1_1") (pintype "passive"))
    )
    (net (code "77") (name "/DATA-PROG1") (class "Default")
      (node (ref "DATA-R/P-SW-0") (pin "6") (pinfunction "2B_6") (pintype "input"))
      (node (ref "PROG/RUN-DATA-SW") (pin "2") (pinfunction "2_2") (pintype "passive"))
    )
    (net (code "78") (name "/DATA-PROG2") (class "Default")
      (node (ref "DATA-R/P-SW-0") (pin "10") (pinfunction "3B_10") (pintype "input"))
      (node (ref "PROG/RUN-DATA-SW") (pin "3") (pinfunction "3_3") (pintype "passive"))
    )
    (net (code "79") (name "/DATA-PROG3") (class "Default")
      (node (ref "DATA-R/P-SW-0") (pin "13") (pinfunction "4B_13") (pintype "input"))
      (node (ref "PROG/RUN-DATA-SW") (pin "4") (pinfunction "4_4") (pintype "passive"))
    )
    (net (code "80") (name "/DATA-PROG4") (class "Default")
      (node (ref "DATA-R/P-SW-1") (pin "3") (pinfunction "1B_3") (pintype "input"))
      (node (ref "PROG/RUN-DATA-SW") (pin "5") (pinfunction "5_5") (pintype "passive"))
    )
    (net (code "81") (name "/DATA-PROG5") (class "Default")
      (node (ref "DATA-R/P-SW-1") (pin "6") (pinfunction "2B_6") (pintype "input"))
      (node (ref "PROG/RUN-DATA-SW") (pin "6") (pinfunction "6_6") (pintype "passive"))
    )
    (net (code "82") (name "/DATA-PROG6") (class "Default")
      (node (ref "DATA-R/P-SW-1") (pin "10") (pinfunction "3B_10") (pintype "input"))
      (node (ref "PROG/RUN-DATA-SW") (pin "7") (pinfunction "7_7") (pintype "passive"))
    )
    (net (code "83") (name "/DATA-PROG7") (class "Default")
      (node (ref "DATA-R/P-SW-1") (pin "13") (pinfunction "4B_13") (pintype "input"))
      (node (ref "PROG/RUN-DATA-SW") (pin "8") (pinfunction "8_8") (pintype "passive"))
    )
    (net (code "86") (name "ADDR-BUS0") (class "Default")
      (node (ref "ADDR-R/P-SW-0") (pin "2") (pinfunction "1A_2") (pintype "input"))
    )
    (net (code "87") (name "ADDR-BUS1") (class "Default")
      (node (ref "ADDR-R/P-SW-0") (pin "5") (pinfunction "2A_5") (pintype "input"))
    )
    (net (code "88") (name "ADDR-BUS2") (class "Default")
      (node (ref "ADDR-R/P-SW-0") (pin "11") (pinfunction "3A_11") (pintype "input"))
    )
    (net (code "89") (name "ADDR-BUS3") (class "Default")
      (node (ref "ADDR-R/P-SW-0") (pin "14") (pinfunction "4A_14") (pintype "input"))
    )
    (net (code "90") (name "ADDR-BUS4") (class "Default")
      (node (ref "ADDR-R/P-SW-1") (pin "2") (pinfunction "1A_2") (pintype "input"))
    )
    (net (code "91") (name "ADDR-BUS5") (class "Default")
      (node (ref "ADDR-R/P-SW-1") (pin "5") (pinfunction "2A_5") (pintype "input"))
    )
    (net (code "92") (name "ADDR-BUS6") (class "Default")
      (node (ref "ADDR-R/P-SW-1") (pin "11") (pinfunction "3A_11") (pintype "input"))
    )
    (net (code "93") (name "ADDR-BUS7") (class "Default")
      (node (ref "ADDR-R/P-SW-1") (pin "14") (pinfunction "4A_14") (pintype "input"))
    )
    (net (code "94") (name "ADDR-BUS12") (class "Default")
      (node (ref "ADDR-R/P-SW-3") (pin "2") (pinfunction "1A_2") (pintype "input"))
      (node (ref "CHIP-SELECT-REG-0") (pin "5") (pinfunction "Q3_5") (pintype "tri_state"))
    )
    (net (code "95") (name "ADDR-PAGE8") (class "Default")
      (node (ref "ADDR-R/P-SW-2") (pin "2") (pinfunction "1A_2") (pintype "input"))
      (node (ref "PAGE-ADDR-REG-0") (pin "3") (pinfunction "Q1_3") (pintype "tri_state"))
    )
    (net (code "96") (name "ADDR-PAGE9") (class "Default")
      (node (ref "ADDR-R/P-SW-2") (pin "5") (pinfunction "2A_5") (pintype "input"))
      (node (ref "PAGE-ADDR-REG-0") (pin "4") (pinfunction "Q2_4") (pintype "tri_state"))
    )
    (net (code "97") (name "ADDR-PAGE10") (class "Default")
      (node (ref "ADDR-R/P-SW-2") (pin "11") (pinfunction "3A_11") (pintype "input"))
      (node (ref "PAGE-ADDR-REG-0") (pin "5") (pinfunction "Q3_5") (pintype "tri_state"))
    )
    (net (code "98") (name "ADDR-PAGE11") (class "Default")
      (node (ref "ADDR-R/P-SW-2") (pin "14") (pinfunction "4A_14") (pintype "input"))
      (node (ref "PAGE-ADDR-REG-0") (pin "6") (pinfunction "Q4_6") (pintype "tri_state"))
    )
    (net (code "99") (name "CLK-SIG") (class "Default")
      (node (ref "CHIP-SELECT-REG-0") (pin "7") (pinfunction "CLK_7") (pintype "input"))
      (node (ref "PAGE-ADDR-REG-0") (pin "7") (pinfunction "CLK_7") (pintype "input"))
    )
    (net (code "100") (name "CS-EN") (class "Default")
      (node (ref "CHIP-SELECT-REG-0") (pin "10") (pinfunction "G2_10") (pintype "input"))
      (node (ref "CHIP-SELECT-REG-0") (pin "9") (pinfunction "G1_9") (pintype "input"))
    )
    (net (code "101") (name "CS0") (class "Default")
      (node (ref "DEMUX-2X4-0") (pin "2") (pinfunction "A_2") (pintype "input"))
    )
    (net (code "102") (name "CS1") (class "Default")
      (node (ref "DEMUX-2X4-0") (pin "3") (pinfunction "B_3") (pintype "input"))
    )
    (net (code "103") (name "DATA-BUS0") (class "Default")
      (node (ref "DATA-R/P-SW-0") (pin "2") (pinfunction "1A_2") (pintype "input"))
    )
    (net (code "104") (name "DATA-BUS1") (class "Default")
      (node (ref "DATA-R/P-SW-0") (pin "5") (pinfunction "2A_5") (pintype "input"))
    )
    (net (code "105") (name "DATA-BUS2") (class "Default")
      (node (ref "DATA-R/P-SW-0") (pin "11") (pinfunction "3A_11") (pintype "input"))
    )
    (net (code "106") (name "DATA-BUS3") (class "Default")
      (node (ref "DATA-R/P-SW-0") (pin "14") (pinfunction "4A_14") (pintype "input"))
    )
    (net (code "107") (name "DATA-BUS4") (class "Default")
      (node (ref "DATA-R/P-SW-1") (pin "2") (pinfunction "1A_2") (pintype "input"))
    )
    (net (code "108") (name "DATA-BUS5") (class "Default")
      (node (ref "DATA-R/P-SW-1") (pin "5") (pinfunction "2A_5") (pintype "input"))
    )
    (net (code "109") (name "DATA-BUS6") (class "Default")
      (node (ref "DATA-R/P-SW-1") (pin "11") (pinfunction "3A_11") (pintype "input"))
    )
    (net (code "110") (name "DATA-BUS7") (class "Default")
      (node (ref "DATA-R/P-SW-1") (pin "14") (pinfunction "4A_14") (pintype "input"))
    )
    (net (code "111") (name "GND") (class "Default")
      (node (ref "ADDR-R/P-SW-0") (pin "15") (pinfunction "G_15") (pintype "input"))
      (node (ref "ADDR-R/P-SW-1") (pin "15") (pinfunction "G_15") (pintype "input"))
      (node (ref "ADDR-R/P-SW-2") (pin "15") (pinfunction "G_15") (pintype "input"))
      (node (ref "ADDR-R/P-SW-3") (pin "10") (pinfunction "3B_10") (pintype "input"))
      (node (ref "ADDR-R/P-SW-3") (pin "11") (pinfunction "3A_11") (pintype "input"))
      (node (ref "ADDR-R/P-SW-3") (pin "12") (pinfunction "4Y_12") (pintype "output"))
      (node (ref "ADDR-R/P-SW-3") (pin "13") (pinfunction "4B_13") (pintype "input"))
      (node (ref "ADDR-R/P-SW-3") (pin "14") (pinfunction "4A_14") (pintype "input"))
      (node (ref "ADDR-R/P-SW-3") (pin "15") (pinfunction "G_15") (pintype "input"))
      (node (ref "ADDR-R/P-SW-3") (pin "5") (pinfunction "2A_5") (pintype "input"))
      (node (ref "ADDR-R/P-SW-3") (pin "6") (pinfunction "2B_6") (pintype "input"))
      (node (ref "ADDR-R/P-SW-3") (pin "7") (pinfunction "2Y_7") (pintype "output"))
      (node (ref "ADDR-R/P-SW-3") (pin "9") (pinfunction "3Y_9") (pintype "output"))
      (node (ref "BUFFER-0") (pin "19") (pinfunction "G_19") (pintype "input"))
      (node (ref "BUFFER-1") (pin "19") (pinfunction "G_19") (pintype "input"))
      (node (ref "BUFFER-3") (pin "11") (pinfunction "B8_11") (pintype "bidirectional"))
      (node (ref "BUFFER-3") (pin "12") (pinfunction "B7_12") (pintype "bidirectional"))
      (node (ref "BUFFER-3") (pin "13") (pinfunction "B6_13") (pintype "bidirectional"))
      (node (ref "BUFFER-3") (pin "14") (pinfunction "B5_14") (pintype "bidirectional"))
      (node (ref "BUFFER-3") (pin "15") (pinfunction "B4_15") (pintype "bidirectional"))
      (node (ref "BUFFER-3") (pin "16") (pinfunction "B3_16") (pintype "bidirectional"))
      (node (ref "BUFFER-3") (pin "17") (pinfunction "B2_17") (pintype "bidirectional"))
      (node (ref "BUFFER-3") (pin "19") (pinfunction "G_19") (pintype "input"))
      (node (ref "BUFFER-3") (pin "3") (pinfunction "A2_3") (pintype "bidirectional"))
      (node (ref "BUFFER-3") (pin "4") (pinfunction "A3_4") (pintype "bidirectional"))
      (node (ref "BUFFER-3") (pin "5") (pinfunction "A4_5") (pintype "bidirectional"))
      (node (ref "BUFFER-3") (pin "6") (pinfunction "A5_6") (pintype "bidirectional"))
      (node (ref "BUFFER-3") (pin "7") (pinfunction "A6_7") (pintype "bidirectional"))
      (node (ref "BUFFER-3") (pin "8") (pinfunction "A7_8") (pintype "bidirectional"))
      (node (ref "BUFFER-3") (pin "9") (pinfunction "A8_9") (pintype "bidirectional"))
      (node (ref "CHIP-SELECT-REG-0") (pin "1") (pinfunction "M_1") (pintype "input"))
      (node (ref "CHIP-SELECT-REG-0") (pin "15") (pinfunction "CLR_15") (pintype "input"))
      (node (ref "CHIP-SELECT-REG-0") (pin "2") (pinfunction "N_2") (pintype "input"))
      (node (ref "CHIP-SELECT-REG-0") (pin "6") (pinfunction "Q4_6") (pintype "tri_state"))
      (node (ref "DATA-R/P-SW-0") (pin "15") (pinfunction "G_15") (pintype "input"))
      (node (ref "DATA-R/P-SW-1") (pin "15") (pinfunction "G_15") (pintype "input"))
      (node (ref "LED1") (pin "K") (pinfunction "C_K") (pintype "passive"))
      (node (ref "LED10") (pin "K") (pinfunction "C_K") (pintype "passive"))
      (node (ref "LED11") (pin "K") (pinfunction "C_K") (pintype "passive"))
      (node (ref "LED12") (pin "K") (pinfunction "C_K") (pintype "passive"))
      (node (ref "LED13") (pin "K") (pinfunction "C_K") (pintype "passive"))
      (node (ref "LED14") (pin "K") (pinfunction "C_K") (pintype "passive"))
      (node (ref "LED15") (pin "K") (pinfunction "C_K") (pintype "passive"))
      (node (ref "LED16") (pin "K") (pinfunction "C_K") (pintype "passive"))
      (node (ref "LED17") (pin "K") (pinfunction "C_K") (pintype "passive"))
      (node (ref "LED18") (pin "K") (pinfunction "C_K") (pintype "passive"))
      (node (ref "LED19") (pin "K") (pinfunction "C_K") (pintype "passive"))
      (node (ref "LED2") (pin "K") (pinfunction "C_K") (pintype "passive"))
      (node (ref "LED20") (pin "K") (pinfunction "C_K") (pintype "passive"))
      (node (ref "LED21") (pin "K") (pinfunction "C_K") (pintype "passive"))
      (node (ref "LED22") (pin "K") (pinfunction "C_K") (pintype "passive"))
      (node (ref "LED23") (pin "K") (pinfunction "C_K") (pintype "passive"))
      (node (ref "LED24") (pin "K") (pinfunction "C_K") (pintype "passive"))
      (node (ref "LED25") (pin "K") (pinfunction "C_K") (pintype "passive"))
      (node (ref "LED3") (pin "K") (pinfunction "C_K") (pintype "passive"))
      (node (ref "LED4") (pin "K") (pinfunction "C_K") (pintype "passive"))
      (node (ref "LED5") (pin "K") (pinfunction "C_K") (pintype "passive"))
      (node (ref "LED6") (pin "K") (pinfunction "C_K") (pintype "passive"))
      (node (ref "LED7") (pin "K") (pinfunction "C_K") (pintype "passive"))
      (node (ref "LED8") (pin "K") (pinfunction "C_K") (pintype "passive"))
      (node (ref "LED9") (pin "K") (pinfunction "C_K") (pintype "passive"))
      (node (ref "MEMORY-0-8KX8-6264") (pin "14") (pinfunction "VSS_14") (pintype "power_in"))
      (node (ref "MEMORY-1-8KX8-6264") (pin "14") (pinfunction "VSS_14") (pintype "power_in"))
      (node (ref "MEMORY-2-8KX8-6264") (pin "14") (pinfunction "VSS_14") (pintype "power_in"))
      (node (ref "MEMORY-3-8KX8-6264") (pin "14") (pinfunction "VSS_14") (pintype "power_in"))
      (node (ref "PAGE-ADDR-REG-0") (pin "1") (pinfunction "M_1") (pintype "input"))
      (node (ref "PAGE-ADDR-REG-0") (pin "15") (pinfunction "CLR_15") (pintype "input"))
      (node (ref "PAGE-ADDR-REG-0") (pin "2") (pinfunction "N_2") (pintype "input"))
      (node (ref "PROG/RUN-ADDR-SW") (pin "13") (pinfunction "13_13") (pintype "passive"))
      (node (ref "PROG/RUN-ADDR-SW") (pin "14") (pinfunction "14_14") (pintype "passive"))
      (node (ref "PROG/RUN-ADDR-SW") (pin "15") (pinfunction "15_15") (pintype "passive"))
      (node (ref "PROG/RUN-ADDR-SW") (pin "16") (pinfunction "16_16") (pintype "passive"))
      (node (ref "PROG/RUN-ADDR-SW") (pin "17") (pinfunction "17_17") (pintype "passive"))
      (node (ref "PROG/RUN-ADDR-SW") (pin "18") (pinfunction "18_18") (pintype "passive"))
      (node (ref "PROG/RUN-ADDR-SW") (pin "19") (pinfunction "19_19") (pintype "passive"))
      (node (ref "PROG/RUN-ADDR-SW") (pin "20") (pinfunction "20_20") (pintype "passive"))
      (node (ref "PROG/RUN-ADDR-SW") (pin "21") (pinfunction "21_21") (pintype "passive"))
      (node (ref "PROG/RUN-ADDR-SW") (pin "22") (pinfunction "22_22") (pintype "passive"))
      (node (ref "PROG/RUN-ADDR-SW") (pin "23") (pinfunction "23_23") (pintype "passive"))
      (node (ref "PROG/RUN-ADDR-SW") (pin "24") (pinfunction "24_24") (pintype "passive"))
      (node (ref "PROG/RUN-DATA-SW") (pin "10") (pinfunction "10_10") (pintype "passive"))
      (node (ref "PROG/RUN-DATA-SW") (pin "11") (pinfunction "11_11") (pintype "passive"))
      (node (ref "PROG/RUN-DATA-SW") (pin "12") (pinfunction "12_12") (pintype "passive"))
      (node (ref "PROG/RUN-DATA-SW") (pin "13") (pinfunction "13_13") (pintype "passive"))
      (node (ref "PROG/RUN-DATA-SW") (pin "14") (pinfunction "14_14") (pintype "passive"))
      (node (ref "PROG/RUN-DATA-SW") (pin "15") (pinfunction "15_15") (pintype "passive"))
      (node (ref "PROG/RUN-DATA-SW") (pin "16") (pinfunction "16_16") (pintype "passive"))
      (node (ref "PROG/RUN-DATA-SW") (pin "9") (pinfunction "9_9") (pintype "passive"))
      (node (ref "SW2") (pin "2") (pinfunction "2_2") (pintype "passive"))
      (node (ref "SW3") (pin "2") (pinfunction "2_2") (pintype "passive"))
    )
    (net (code "112") (name "MRQ") (class "Default")
      (node (ref "BUFFER-2") (pin "19") (pinfunction "G_19") (pintype "input"))
      (node (ref "DEMUX-2X4-0") (pin "1") (pinfunction "G_1") (pintype "input"))
    )
    (net (code "113") (name "PR-LOAD") (class "Default")
      (node (ref "PAGE-ADDR-REG-0") (pin "10") (pinfunction "G2_10") (pintype "input"))
      (node (ref "PAGE-ADDR-REG-0") (pin "9") (pinfunction "G1_9") (pintype "input"))
    )
    (net (code "114") (name "PROG{slash}BUS-SW") (class "Default")
      (node (ref "ADDR-R/P-SW-0") (pin "1") (pinfunction "~{A}/B_1") (pintype "input"))
      (node (ref "ADDR-R/P-SW-1") (pin "1") (pinfunction "~{A}/B_1") (pintype "input"))
      (node (ref "ADDR-R/P-SW-2") (pin "1") (pinfunction "~{A}/B_1") (pintype "input"))
      (node (ref "ADDR-R/P-SW-3") (pin "1") (pinfunction "~{A}/B_1") (pintype "input"))
      (node (ref "DATA-R/P-SW-0") (pin "1") (pinfunction "~{A}/B_1") (pintype "input"))
      (node (ref "DATA-R/P-SW-1") (pin "1") (pinfunction "~{A}/B_1") (pintype "input"))
      (node (ref "SW2") (pin "1") (pinfunction "1_1") (pintype "passive"))
    )
    (net (code "115") (name "RD") (class "Default")
      (node (ref "MEMORY-0-8KX8-6264") (pin "22") (pinfunction "~{OE}_22") (pintype "input"))
      (node (ref "MEMORY-1-8KX8-6264") (pin "22") (pinfunction "~{OE}_22") (pintype "input"))
      (node (ref "MEMORY-2-8KX8-6264") (pin "22") (pinfunction "~{OE}_22") (pintype "input"))
      (node (ref "MEMORY-3-8KX8-6264") (pin "22") (pinfunction "~{OE}_22") (pintype "input"))
    )
    (net (code "116") (name "VCC") (class "Default")
      (node (ref "BUFFER-0") (pin "1") (pinfunction "DIR_1") (pintype "input"))
      (node (ref "BUFFER-1") (pin "1") (pinfunction "DIR_1") (pintype "input"))
      (node (ref "BUFFER-3") (pin "1") (pinfunction "DIR_1") (pintype "input"))
      (node (ref "MEMORY-0-8KX8-6264") (pin "26") (pinfunction "CS2_26") (pintype "input"))
      (node (ref "MEMORY-0-8KX8-6264") (pin "28") (pinfunction "VCC_28") (pintype "power_in"))
      (node (ref "MEMORY-1-8KX8-6264") (pin "26") (pinfunction "CS2_26") (pintype "input"))
      (node (ref "MEMORY-1-8KX8-6264") (pin "28") (pinfunction "VCC_28") (pintype "power_in"))
      (node (ref "MEMORY-2-8KX8-6264") (pin "26") (pinfunction "CS2_26") (pintype "input"))
      (node (ref "MEMORY-2-8KX8-6264") (pin "28") (pinfunction "VCC_28") (pintype "power_in"))
      (node (ref "MEMORY-3-8KX8-6264") (pin "26") (pinfunction "CS2_26") (pintype "input"))
      (node (ref "MEMORY-3-8KX8-6264") (pin "28") (pinfunction "VCC_28") (pintype "power_in"))
    )
    (net (code "117") (name "WR") (class "Default")
      (node (ref "BUFFER-2") (pin "1") (pinfunction "DIR_1") (pintype "input"))
      (node (ref "MEMORY-0-8KX8-6264") (pin "27") (pinfunction "~{WE}_27") (pintype "input"))
      (node (ref "MEMORY-1-8KX8-6264") (pin "27") (pinfunction "~{WE}_27") (pintype "input"))
      (node (ref "MEMORY-2-8KX8-6264") (pin "27") (pinfunction "~{WE}_27") (pintype "input"))
      (node (ref "MEMORY-3-8KX8-6264") (pin "27") (pinfunction "~{WE}_27") (pintype "input"))
    )
    (net (code "118") (name "unconnected-(CHIP-SELECT-REG-0A-Q1-Pad3)") (class "Default")
      (node (ref "CHIP-SELECT-REG-0") (pin "3") (pinfunction "Q1_3") (pintype "tri_state"))
    )
    (net (code "119") (name "unconnected-(CHIP-SELECT-REG-0A-Q2-Pad4)") (class "Default")
      (node (ref "CHIP-SELECT-REG-0") (pin "4") (pinfunction "Q2_4") (pintype "tri_state"))
    )
    (net (code "120") (name "unconnected-(MEMORY-0-8KX8-6264-NC-Pad1)") (class "Default")
      (node (ref "MEMORY-0-8KX8-6264") (pin "1") (pinfunction "NC_1") (pintype "no_connect"))
    )
    (net (code "121") (name "unconnected-(MEMORY-1-8KX8-6264-NC-Pad1)") (class "Default")
      (node (ref "MEMORY-1-8KX8-6264") (pin "1") (pinfunction "NC_1") (pintype "no_connect"))
    )
    (net (code "122") (name "unconnected-(MEMORY-2-8KX8-6264-NC-Pad1)") (class "Default")
      (node (ref "MEMORY-2-8KX8-6264") (pin "1") (pinfunction "NC_1") (pintype "no_connect"))
    )
    (net (code "123") (name "unconnected-(MEMORY-3-8KX8-6264-NC-Pad1)") (class "Default")
      (node (ref "MEMORY-3-8KX8-6264") (pin "1") (pinfunction "NC_1") (pintype "no_connect"))
    )
  )
)
